# daisy-chain_isolation.net
KiCad netlist of a schematic drawn in Altium Designer
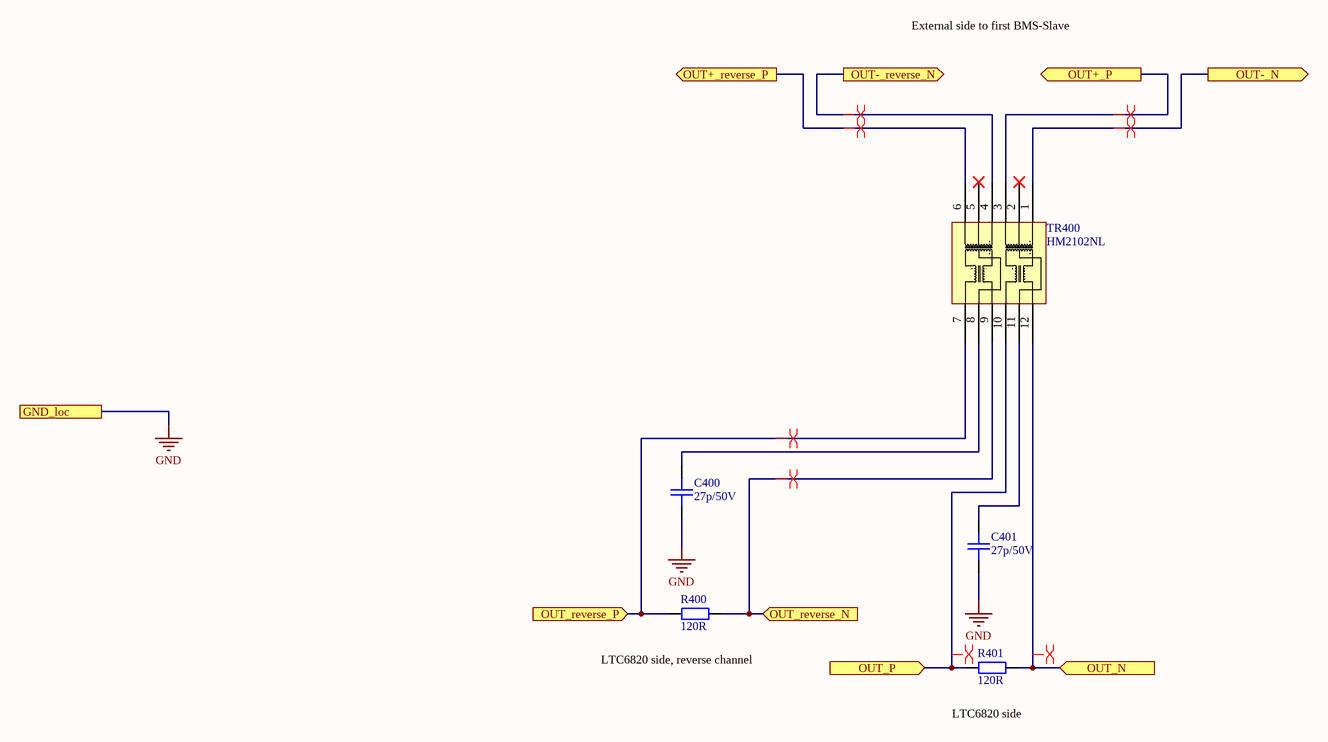
[diagram p0: daisy-chain_isolation.SchDoc]

(export (version "E")
  (design (tool "Eeschema 10.0.6"))
  (components
    (comp (ref "C400")
      (value "27p/50V")
      (footprint "CAPC1608X08N")
      (description "MLCC")
      (fields (field (name "PART NUMBER") "gen_C_ceramic_27p_50V_NP0_0603"))
      (libsource (lib "OE750") (part "C"))
    )
    (comp (ref "C401")
      (value "27p/50V")
      (footprint "CAPC1608X08N")
      (description "MLCC")
      (fields (field (name "PART NUMBER") "gen_C_ceramic_27p_50V_NP0_0603"))
      (libsource (lib "OE750") (part "C"))
    )
    (comp (ref "R400")
      (value "120R")
      (footprint "RESC1608X05N")
      (description "SMD Resistor 120R 0603")
      (fields (field (name "PART NUMBER") "gen_R_120R_0603") (field (name "TOLERANCE") "1%"))
      (libsource (lib "OE750") (part "R"))
    )
    (comp (ref "R401")
      (value "120R")
      (footprint "RESC1608X05N")
      (description "SMD Resistor 120R 0603")
      (fields (field (name "PART NUMBER") "gen_R_120R_0603") (field (name "TOLERANCE") "1%"))
      (libsource (lib "OE750") (part "R"))
    )
    (comp (ref "TR400")
      (value "HM2102NL")
      (footprint "HM2102NL")
      (description "Pulse HM2102NL BMS Transformer")
      (fields (field (name "MANUFACTURER") "Pulse"))
      (libsource (lib "OE750") (part "HM2102NL"))
    )
  )
  (nets
    (net (code "1") (name "/OUT+_P") (class "Default") (node (ref "TR400") (pin "3") (pintype "passive")))
    (net (code "2") (name "/OUT+_reverse_P") (class "Default")
      (node (ref "TR400") (pin "6") (pintype "passive"))
    )
    (net (code "3") (name "/OUT-_N") (class "Default") (node (ref "TR400") (pin "1") (pintype "passive")))
    (net (code "4") (name "/OUT-_reverse_N") (class "Default")
      (node (ref "TR400") (pin "4") (pintype "passive"))
    )
    (net (code "5") (name "/OUT_N") (class "Default")
      (node (ref "R401") (pin "2") (pinfunction "2_2") (pintype "passive"))
      (node (ref "TR400") (pin "12") (pintype "passive"))
    )
    (net (code "6") (name "/OUT_P") (class "Default")
      (node (ref "R401") (pin "1") (pinfunction "1_1") (pintype "passive"))
      (node (ref "TR400") (pin "10") (pintype "passive"))
    )
    (net (code "7") (name "/OUT_reverse_N") (class "Default")
      (node (ref "R400") (pin "2") (pinfunction "2_2") (pintype "passive"))
      (node (ref "TR400") (pin "9") (pintype "passive"))
    )
    (net (code "8") (name "/OUT_reverse_P") (class "Default")
      (node (ref "R400") (pin "1") (pinfunction "1_1") (pintype "passive"))
      (node (ref "TR400") (pin "7") (pintype "passive"))
    )
    (net (code "9") (name "GND") (class "Default")
      (node (ref "C400") (pin "1") (pinfunction "1_1") (pintype "passive"))
      (node (ref "C401") (pin "1") (pinfunction "1_1") (pintype "passive"))
    )
    (net (code "10") (name "Net-(C400-Pad2)") (class "Default")
      (node (ref "C400") (pin "2") (pinfunction "2_2") (pintype "passive"))
      (node (ref "TR400") (pin "8") (pintype "passive"))
    )
    (net (code "11") (name "Net-(C401-Pad2)") (class "Default")
      (node (ref "C401") (pin "2") (pinfunction "2_2") (pintype "passive"))
      (node (ref "TR400") (pin "11") (pintype "passive"))
    )
    (net (code "12") (name "unconnected-(TR400-Pad2)") (class "Default")
      (node (ref "TR400") (pin "2") (pintype "passive+no_connect"))
    )
    (net (code "13") (name "unconnected-(TR400-Pad5)") (class "Default")
      (node (ref "TR400") (pin "5") (pintype "passive+no_connect"))
    )
  )
)
